# TM.net
KiCad netlist of a schematic drawn in Altium Designer
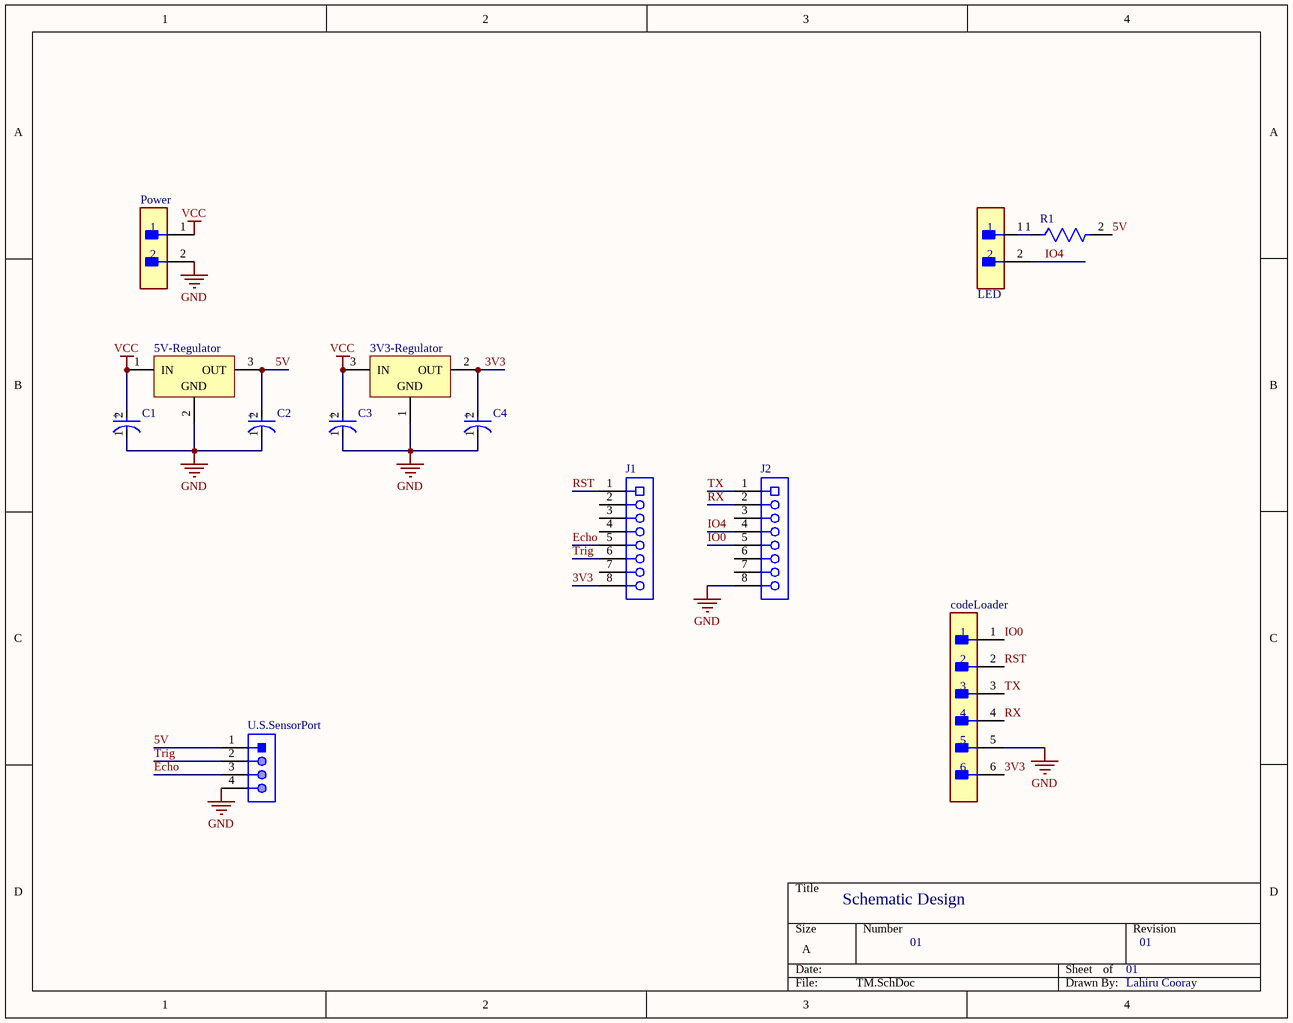
[diagram p0: TM.SchDoc]

(export (version "E")
  (design (tool "Eeschema 10.0.6"))
  (components
    (comp (ref "3V3-Regulator")
      (value "LM1117T-3.3/NOPB")
      (footprint "NDE0003A")
      (description "800mA Low-Dropout Linear Regulator, 3-pin TO-220, Pb-Free")
      (fields (field (name "MANUFACTURER") "Texas Instruments"))
      (libsource (lib "Altium Content Vault") (part "PM-REG-LM1086-SIL3"))
    )
    (comp (ref "5V-Regulator")
      (value "L7805CV")
      (footprint "TO220")
      (description "Positive Voltage Regulator, 5V, 3-Pin TO-220")
      (libsource (lib "Altium Content Vault") (part "PM-REG-L4940-SIL3"))
    )
    (comp (ref "C1")
      (value "EEUHD1H330")
      (footprint "FP-RAD-TH-D_5_0_5-L_11_1-MFG")
      (description "Aluminum Electrolytic Capacitors (Radial Lead Type) AEC-Q200 Qualified 33uF ±20% 50V")
      (fields (field (name "TOLERANCE") "20%") (field (name "VOLTAGE") "50V"))
      (libsource (lib "Altium Content Vault") (part "a00bbbee19879c290e62620ae7e47b1"))
    )
    (comp (ref "C2")
      (value "EEUHD1H330")
      (footprint "FP-RAD-TH-D_5_0_5-L_11_1-MFG")
      (description "Aluminum Electrolytic Capacitors (Radial Lead Type) AEC-Q200 Qualified 33uF ±20% 50V")
      (fields (field (name "TOLERANCE") "20%") (field (name "VOLTAGE") "50V"))
      (libsource (lib "Altium Content Vault") (part "a00bbbee19879c290e62620ae7e47b1"))
    )
    (comp (ref "C3")
      (value "EEUHD1H330")
      (footprint "FP-RAD-TH-D_5_0_5-L_11_1-MFG")
      (description "Aluminum Electrolytic Capacitors (Radial Lead Type) AEC-Q200 Qualified 33uF ±20% 50V")
      (fields (field (name "TOLERANCE") "20%") (field (name "VOLTAGE") "50V"))
      (libsource (lib "Altium Content Vault") (part "a00bbbee19879c290e62620ae7e47b1"))
    )
    (comp (ref "C4")
      (value "EEUHD1H330")
      (footprint "FP-RAD-TH-D_5_0_5-L_11_1-MFG")
      (description "Aluminum Electrolytic Capacitors (Radial Lead Type) AEC-Q200 Qualified 33uF ±20% 50V")
      (fields (field (name "TOLERANCE") "20%") (field (name "VOLTAGE") "50V"))
      (libsource (lib "Altium Content Vault") (part "a00bbbee19879c290e62620ae7e47b1"))
    )
    (comp (ref "codeLoader")
      (value "22-28-4063")
      (footprint "FP-22-28-4063-MFG")
      (description "CONN HEADER VERT 6POS 2.54MM")
      (libsource (lib "Altium Content Vault") (part "f2cb566baf1c37ab5a3b8e90bbeafd6"))
    )
    (comp (ref "J1")
      (value "PPPC081LFBN-RC")
      (footprint "SLIN-PPPC081LFBN-RC_V")
      (libsource (lib "Altium Content Vault") (part "CN-1P-F-R8"))
    )
    (comp (ref "J2")
      (value "PPPC081LFBN-RC")
      (footprint "SLIN-PPPC081LFBN-RC_V")
      (libsource (lib "Altium Content Vault") (part "CN-1P-F-R8"))
    )
    (comp (ref "LED")
      (value "M20-9990246")
      (footprint "FP-M20-9990246-MFG")
      (description "CONN HEADER VERT 2POS 2.54MM")
      (fields
        (field (name "OCTOPART") "https://octopart.com/m20-9990246-harwin-2590635")
        (field (name "MANUFACTURER") "Harwin")
      )
      (libsource (lib "Altium Content Vault") (part "3bc925449376181038e59eaffc5286c"))
    )
    (comp (ref "Power")
      (value "M20-9990246")
      (footprint "FP-M20-9990246-MFG")
      (description "CONN HEADER VERT 2POS 2.54MM")
      (fields
        (field (name "OCTOPART") "https://octopart.com/m20-9990246-harwin-2590635")
        (field (name "MANUFACTURER") "Harwin")
      )
      (libsource (lib "Altium Content Vault") (part "3bc925449376181038e59eaffc5286c"))
    )
    (comp (ref "R1")
      (value "MRS25000C9530FCT00")
      (footprint "FP-MRS25-MFG")
      (description "RES 953 OHM 0.6W 1% AXIAL")
      (fields (field (name "TOLERANCE") "1%"))
      (libsource (lib "Altium Content Vault") (part "1029c3af85768c4190bb7ad29bc67b5"))
    )
    (comp (ref "U.S.SensorPort")
      (value "61300411121")
      (footprint "61300411121")
      (description "THT Vertical Pin Header WR-PHD, Pitch 2.54 mm, Single Row, 4 pins")
      (fields (field (name "MANUFACTURER") "Wurth Elektronik") (field (name "PUBLISHER") "WurthElektronik"))
      (libsource (lib "Altium Content Vault") (part "WE-CN-1P-M-R4"))
    )
  )
  (nets
    (net (code "1") (name "/3V3") (class "Default")
      (node (ref "3V3-Regulator") (pin "2") (pinfunction "OUT_2") (pintype "power_in"))
      (node (ref "C4") (pin "2") (pinfunction "A_2") (pintype "passive"))
      (node (ref "J1") (pin "8") (pinfunction "8_8") (pintype "passive"))
      (node (ref "codeLoader") (pin "6") (pinfunction "6_6") (pintype "passive"))
    )
    (net (code "2") (name "/5V") (class "Default")
      (node (ref "5V-Regulator") (pin "3") (pinfunction "OUT_3") (pintype "power_in"))
      (node (ref "C2") (pin "2") (pinfunction "A_2") (pintype "passive"))
      (node (ref "R1") (pin "2") (pinfunction "2_2") (pintype "passive"))
      (node (ref "U.S.SensorPort") (pin "1") (pinfunction "1_1") (pintype "passive"))
    )
    (net (code "3") (name "/Echo") (class "Default")
      (node (ref "J1") (pin "5") (pinfunction "5_5") (pintype "passive"))
      (node (ref "U.S.SensorPort") (pin "3") (pinfunction "3_3") (pintype "passive"))
    )
    (net (code "4") (name "/IO0") (class "Default")
      (node (ref "J2") (pin "5") (pinfunction "5_5") (pintype "passive"))
      (node (ref "codeLoader") (pin "1") (pinfunction "1_1") (pintype "passive"))
    )
    (net (code "5") (name "/IO4") (class "Default")
      (node (ref "J2") (pin "4") (pinfunction "4_4") (pintype "passive"))
      (node (ref "LED") (pin "2") (pinfunction "2_2") (pintype "passive"))
    )
    (net (code "6") (name "/RST") (class "Default")
      (node (ref "J1") (pin "1") (pinfunction "1_1") (pintype "passive"))
      (node (ref "codeLoader") (pin "2") (pinfunction "2_2") (pintype "passive"))
    )
    (net (code "7") (name "/RX") (class "Default")
      (node (ref "J2") (pin "2") (pinfunction "2_2") (pintype "passive"))
      (node (ref "codeLoader") (pin "4") (pinfunction "4_4") (pintype "passive"))
    )
    (net (code "8") (name "/TX") (class "Default")
      (node (ref "J2") (pin "1") (pinfunction "1_1") (pintype "passive"))
      (node (ref "codeLoader") (pin "3") (pinfunction "3_3") (pintype "passive"))
    )
    (net (code "9") (name "/Trig") (class "Default")
      (node (ref "J1") (pin "6") (pinfunction "6_6") (pintype "passive"))
      (node (ref "U.S.SensorPort") (pin "2") (pinfunction "2_2") (pintype "passive"))
    )
    (net (code "10") (name "GND") (class "Default")
      (node (ref "3V3-Regulator") (pin "1") (pinfunction "GND_1") (pintype "power_in"))
      (node (ref "5V-Regulator") (pin "2") (pinfunction "GND_2") (pintype "power_in"))
      (node (ref "C1") (pin "1") (pinfunction "C_1") (pintype "passive"))
      (node (ref "C2") (pin "1") (pinfunction "C_1") (pintype "passive"))
      (node (ref "C3") (pin "1") (pinfunction "C_1") (pintype "passive"))
      (node (ref "C4") (pin "1") (pinfunction "C_1") (pintype "passive"))
      (node (ref "J2") (pin "8") (pinfunction "8_8") (pintype "passive"))
      (node (ref "Power") (pin "2") (pinfunction "2_2") (pintype "passive"))
      (node (ref "U.S.SensorPort") (pin "4") (pinfunction "4_4") (pintype "passive"))
      (node (ref "codeLoader") (pin "5") (pinfunction "5_5") (pintype "passive"))
    )
    (net (code "11") (name "Net-(LED-Pad1)") (class "Default")
      (node (ref "LED") (pin "1") (pinfunction "1_1") (pintype "passive"))
      (node (ref "R1") (pin "1") (pinfunction "1_1") (pintype "passive"))
    )
    (net (code "12") (name "VCC") (class "Default")
      (node (ref "3V3-Regulator") (pin "3") (pinfunction "IN_3") (pintype "power_in"))
      (node (ref "5V-Regulator") (pin "1") (pinfunction "IN_1") (pintype "power_in"))
      (node (ref "C1") (pin "2") (pinfunction "A_2") (pintype "passive"))
      (node (ref "C3") (pin "2") (pinfunction "A_2") (pintype "passive"))
      (node (ref "Power") (pin "1") (pinfunction "1_1") (pintype "passive"))
    )
    (net (code "13") (name "unconnected-(J1-Pad2)") (class "Default")
      (node (ref "J1") (pin "2") (pinfunction "2_2") (pintype "passive"))
    )
    (net (code "14") (name "unconnected-(J1-Pad3)") (class "Default")
      (node (ref "J1") (pin "3") (pinfunction "3_3") (pintype "passive"))
    )
    (net (code "15") (name "unconnected-(J1-Pad4)") (class "Default")
      (node (ref "J1") (pin "4") (pinfunction "4_4") (pintype "passive"))
    )
    (net (code "16") (name "unconnected-(J1-Pad7)") (class "Default")
      (node (ref "J1") (pin "7") (pinfunction "7_7") (pintype "passive"))
    )
    (net (code "17") (name "unconnected-(J2-Pad3)") (class "Default")
      (node (ref "J2") (pin "3") (pinfunction "3_3") (pintype "passive"))
    )
    (net (code "18") (name "unconnected-(J2-Pad6)") (class "Default")
      (node (ref "J2") (pin "6") (pinfunction "6_6") (pintype "passive"))
    )
    (net (code "19") (name "unconnected-(J2-Pad7)") (class "Default")
      (node (ref "J2") (pin "7") (pinfunction "7_7") (pintype "passive"))
    )
  )
)
